# CoproMKII_Actuator.net
KiCad netlist of a schematic drawn in Altium Designer
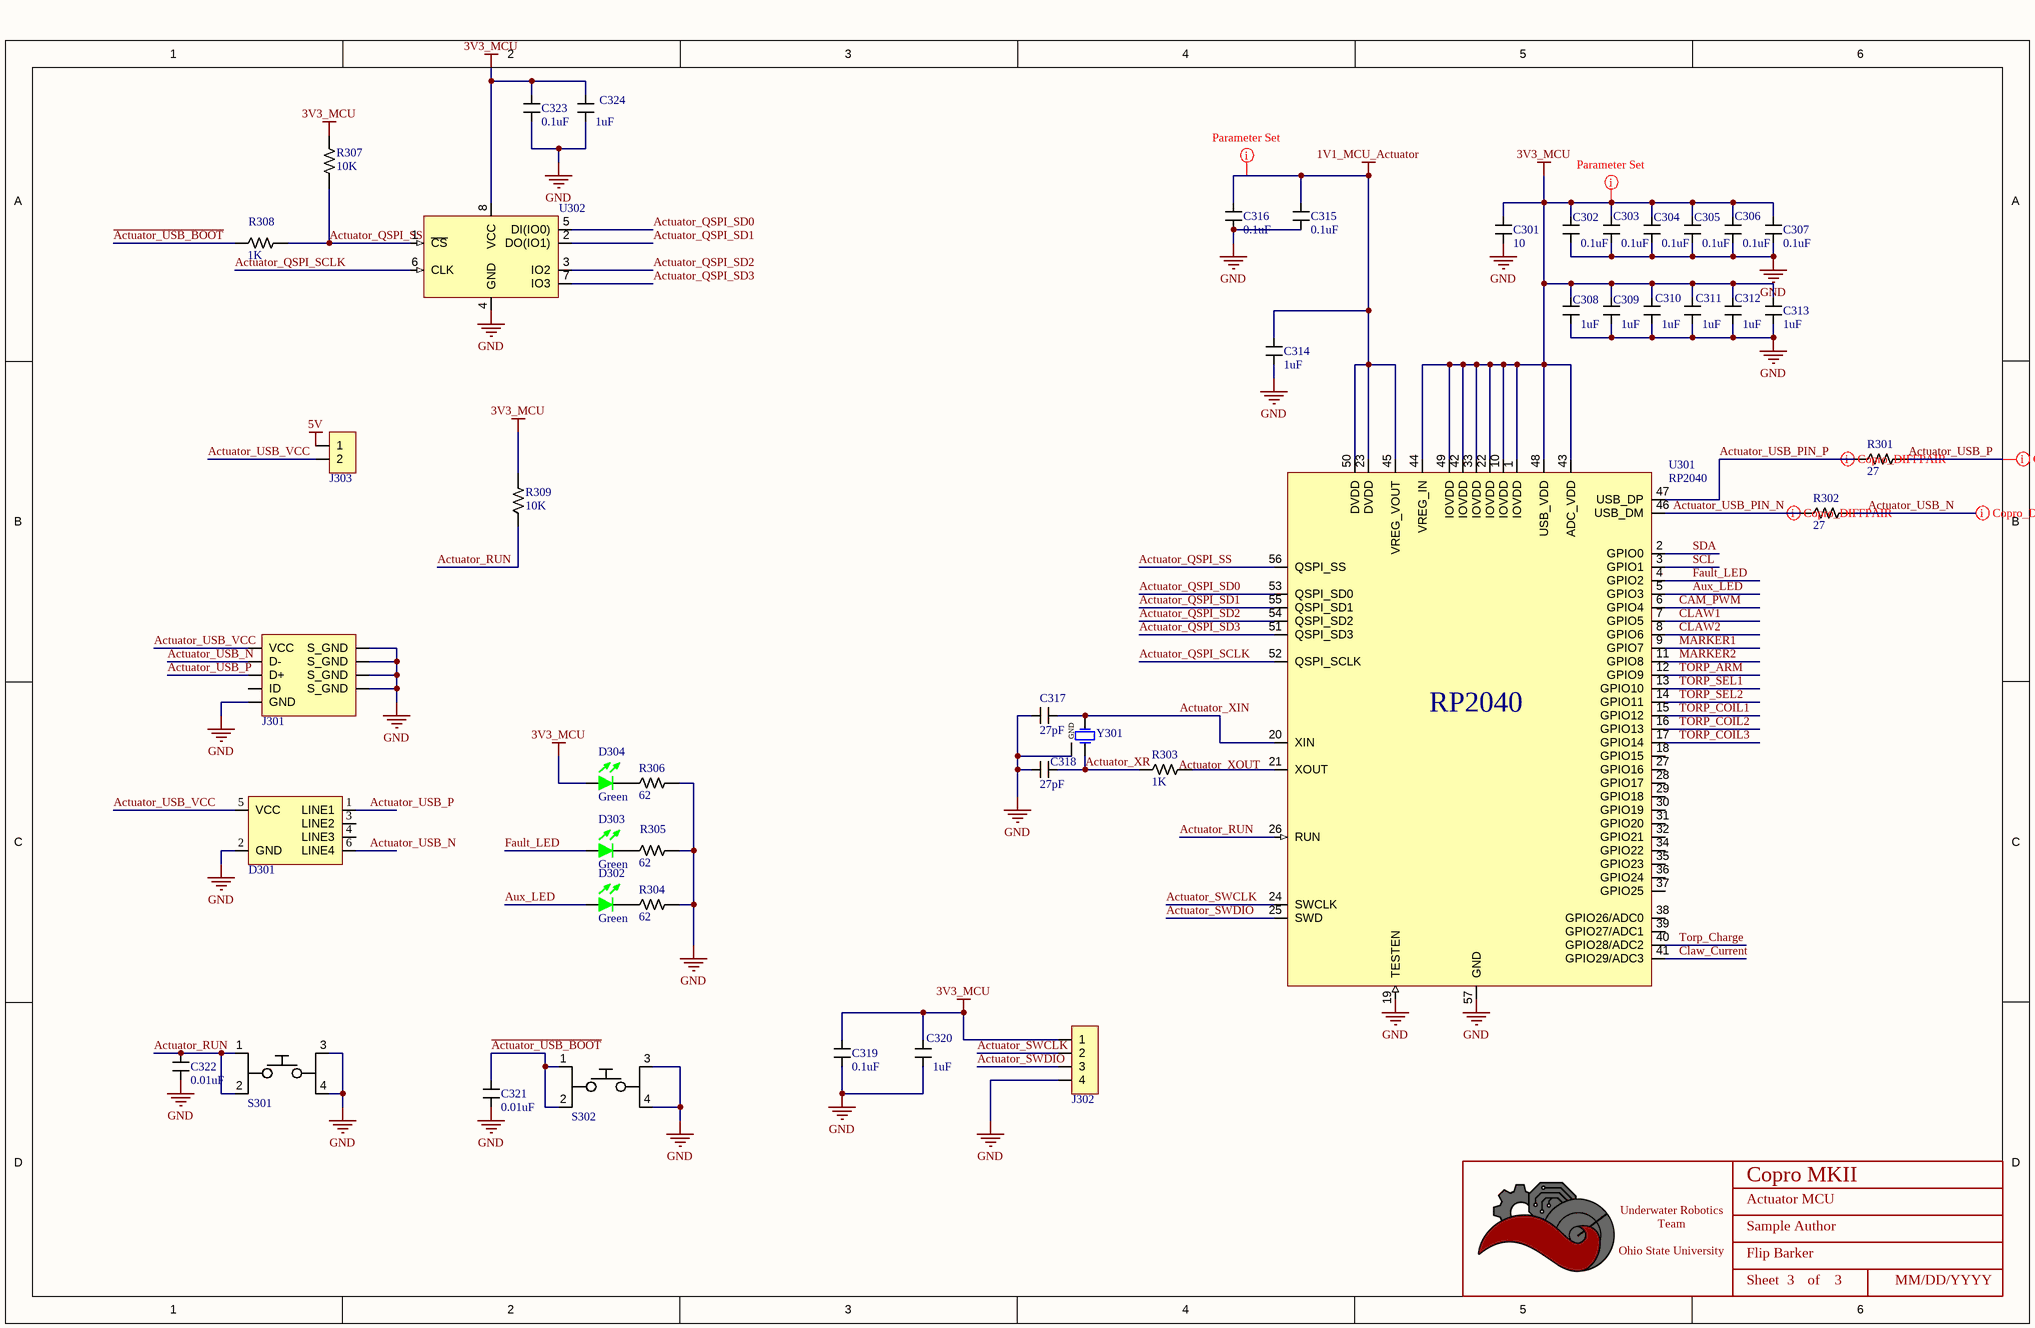
[diagram p0: CoproMKII_Actuator.SchDoc]

(export (version "E")
  (design (tool "Eeschema 10.0.6"))
  (components
    (comp (ref "C301")
      (value "10uF Ceramic 6.3V")
      (footprint "CAPACITOR_0603")
      (description "Cap 10uF 6.3V +/-20%\r\nCeramic 0603")
      (fields
        (field (name "TOLERANCE") "+/- 20%")
        (field (name "VOLTAGE") "6.3V")
        (field (name "VALUE (UF)") "10")
        (field (name "MADE BY") "Flip B")
      )
      (libsource (lib "Capacitors") (part "CAPACITOR_10uF_0603"))
    )
    (comp (ref "C302")
      (value "0.1uF")
      (footprint "CAPACITOR_0603")
      (description "Cap 100nF 6.3V +/-10%\r\nCeramic 0603")
      (fields
        (field (name "TOLERANCE") "+/- 10%")
        (field (name "VOLTAGE") "6.3V")
        (field (name "MADE BY") "Flip B")
      )
      (libsource (lib "Capacitors") (part "CAPACITOR_0.1uF_0603"))
    )
    (comp (ref "C303")
      (value "0.1uF")
      (footprint "CAPACITOR_0603")
      (description "Cap 100nF 6.3V +/-10%\r\nCeramic 0603")
      (fields
        (field (name "TOLERANCE") "+/- 10%")
        (field (name "VOLTAGE") "6.3V")
        (field (name "MADE BY") "Flip B")
      )
      (libsource (lib "Capacitors") (part "CAPACITOR_0.1uF_0603"))
    )
    (comp (ref "C304")
      (value "0.1uF")
      (footprint "CAPACITOR_0603")
      (description "Cap 100nF 6.3V +/-10%\r\nCeramic 0603")
      (fields
        (field (name "TOLERANCE") "+/- 10%")
        (field (name "VOLTAGE") "6.3V")
        (field (name "MADE BY") "Flip B")
      )
      (libsource (lib "Capacitors") (part "CAPACITOR_0.1uF_0603"))
    )
    (comp (ref "C305")
      (value "0.1uF")
      (footprint "CAPACITOR_0603")
      (description "Cap 100nF 6.3V +/-10%\r\nCeramic 0603")
      (fields
        (field (name "TOLERANCE") "+/- 10%")
        (field (name "VOLTAGE") "6.3V")
        (field (name "MADE BY") "Flip B")
      )
      (libsource (lib "Capacitors") (part "CAPACITOR_0.1uF_0603"))
    )
    (comp (ref "C306")
      (value "0.1uF")
      (footprint "CAPACITOR_0603")
      (description "Cap 100nF 6.3V +/-10%\r\nCeramic 0603")
      (fields
        (field (name "TOLERANCE") "+/- 10%")
        (field (name "VOLTAGE") "6.3V")
        (field (name "MADE BY") "Flip B")
      )
      (libsource (lib "Capacitors") (part "CAPACITOR_0.1uF_0603"))
    )
    (comp (ref "C307")
      (value "0.1uF")
      (footprint "CAPACITOR_0603")
      (description "Cap 100nF 6.3V +/-10%\r\nCeramic 0603")
      (fields
        (field (name "TOLERANCE") "+/- 10%")
        (field (name "VOLTAGE") "6.3V")
        (field (name "MADE BY") "Flip B")
      )
      (libsource (lib "Capacitors") (part "CAPACITOR_0.1uF_0603"))
    )
    (comp (ref "C308")
      (value "1uF")
      (footprint "CAPACITOR_0603")
      (description "Cap 1uF 16V +/-10%\r\nCeramic 0603")
      (fields
        (field (name "TOLERANCE") "+/- 10%")
        (field (name "VOLTAGE") "16V")
        (field (name "MADE BY") "Flip B")
      )
      (libsource (lib "Capacitors") (part "CAPACITOR_1uF_0603"))
    )
    (comp (ref "C309")
      (value "1uF")
      (footprint "CAPACITOR_0603")
      (description "Cap 1uF 16V +/-10%\r\nCeramic 0603")
      (fields
        (field (name "TOLERANCE") "+/- 10%")
        (field (name "VOLTAGE") "16V")
        (field (name "MADE BY") "Flip B")
      )
      (libsource (lib "Capacitors") (part "CAPACITOR_1uF_0603"))
    )
    (comp (ref "C310")
      (value "1uF")
      (footprint "CAPACITOR_0603")
      (description "Cap 1uF 16V +/-10%\r\nCeramic 0603")
      (fields
        (field (name "TOLERANCE") "+/- 10%")
        (field (name "VOLTAGE") "16V")
        (field (name "MADE BY") "Flip B")
      )
      (libsource (lib "Capacitors") (part "CAPACITOR_1uF_0603"))
    )
    (comp (ref "C311")
      (value "1uF")
      (footprint "CAPACITOR_0603")
      (description "Cap 1uF 16V +/-10%\r\nCeramic 0603")
      (fields
        (field (name "TOLERANCE") "+/- 10%")
        (field (name "VOLTAGE") "16V")
        (field (name "MADE BY") "Flip B")
      )
      (libsource (lib "Capacitors") (part "CAPACITOR_1uF_0603"))
    )
    (comp (ref "C312")
      (value "1uF")
      (footprint "CAPACITOR_0603")
      (description "Cap 1uF 16V +/-10%\r\nCeramic 0603")
      (fields
        (field (name "TOLERANCE") "+/- 10%")
        (field (name "VOLTAGE") "16V")
        (field (name "MADE BY") "Flip B")
      )
      (libsource (lib "Capacitors") (part "CAPACITOR_1uF_0603"))
    )
    (comp (ref "C313")
      (value "1uF")
      (footprint "CAPACITOR_0603")
      (description "Cap 1uF 16V +/-10%\r\nCeramic 0603")
      (fields
        (field (name "TOLERANCE") "+/- 10%")
        (field (name "VOLTAGE") "16V")
        (field (name "MADE BY") "Flip B")
      )
      (libsource (lib "Capacitors") (part "CAPACITOR_1uF_0603"))
    )
    (comp (ref "C314")
      (value "1uF")
      (footprint "CAPACITOR_0603")
      (description "Cap 1uF 16V +/-10%\r\nCeramic 0603")
      (fields
        (field (name "TOLERANCE") "+/- 10%")
        (field (name "VOLTAGE") "16V")
        (field (name "MADE BY") "Flip B")
      )
      (libsource (lib "Capacitors") (part "CAPACITOR_1uF_0603"))
    )
    (comp (ref "C315")
      (value "0.1uF")
      (footprint "CAPACITOR_0603")
      (description "Cap 100nF 6.3V +/-10%\r\nCeramic 0603")
      (fields
        (field (name "TOLERANCE") "+/- 10%")
        (field (name "VOLTAGE") "6.3V")
        (field (name "MADE BY") "Flip B")
      )
      (libsource (lib "Capacitors") (part "CAPACITOR_0.1uF_0603"))
    )
    (comp (ref "C316")
      (value "0.1uF")
      (footprint "CAPACITOR_0603")
      (description "Cap 100nF 6.3V +/-10%\r\nCeramic 0603")
      (fields
        (field (name "TOLERANCE") "+/- 10%")
        (field (name "VOLTAGE") "6.3V")
        (field (name "MADE BY") "Flip B")
      )
      (libsource (lib "Capacitors") (part "CAPACITOR_0.1uF_0603"))
    )
    (comp (ref "C317")
      (value "27pF")
      (footprint "CAPACITOR_0603")
      (description "Cap 27pF 50V +/-5%\r\nCeramic 0603")
      (fields
        (field (name "TOLERANCE") "+/- 5%")
        (field (name "VOLTAGE") "50V")
        (field (name "MADE BY") "Flip B")
      )
      (libsource (lib "Capacitors") (part "CAPACITOR_0.000027uF_0603"))
    )
    (comp (ref "C318")
      (value "27pF")
      (footprint "CAPACITOR_0603")
      (description "Cap 27pF 50V +/-5%\r\nCeramic 0603")
      (fields
        (field (name "TOLERANCE") "+/- 5%")
        (field (name "VOLTAGE") "50V")
        (field (name "MADE BY") "Flip B")
      )
      (libsource (lib "Capacitors") (part "CAPACITOR_0.000027uF_0603"))
    )
    (comp (ref "C319")
      (value "0.1uF")
      (footprint "CAPACITOR_0603")
      (description "Cap 100nF 6.3V +/-10%\r\nCeramic 0603")
      (fields
        (field (name "TOLERANCE") "+/- 10%")
        (field (name "VOLTAGE") "6.3V")
        (field (name "MADE BY") "Flip B")
      )
      (libsource (lib "Capacitors") (part "CAPACITOR_0.1uF_0603"))
    )
    (comp (ref "C320")
      (value "1uF")
      (footprint "CAPACITOR_0603")
      (description "Cap 1uF 16V +/-10%\r\nCeramic 0603")
      (fields
        (field (name "TOLERANCE") "+/- 10%")
        (field (name "VOLTAGE") "16V")
        (field (name "MADE BY") "Flip B")
      )
      (libsource (lib "Capacitors") (part "CAPACITOR_1uF_0603"))
    )
    (comp (ref "C321")
      (value "0.01uF")
      (footprint "CAPACITOR_0603")
      (description "Cap 10nF 6.3V +/-20%\r\nCeramic 0603")
      (fields
        (field (name "TOLERANCE") "+/- 10%")
        (field (name "VOLTAGE") "6.3V")
        (field (name "MADE BY") "Flip B")
      )
      (libsource (lib "Capacitors") (part "CAPACITOR_0.01uF_0603"))
    )
    (comp (ref "C322")
      (value "0.01uF")
      (footprint "CAPACITOR_0603")
      (description "Cap 10nF 6.3V +/-20%\r\nCeramic 0603")
      (fields
        (field (name "TOLERANCE") "+/- 10%")
        (field (name "VOLTAGE") "6.3V")
        (field (name "MADE BY") "Flip B")
      )
      (libsource (lib "Capacitors") (part "CAPACITOR_0.01uF_0603"))
    )
    (comp (ref "C323")
      (value "0.1uF")
      (footprint "CAPACITOR_0603")
      (description "Cap 100nF 6.3V +/-10%\r\nCeramic 0603")
      (fields
        (field (name "TOLERANCE") "+/- 10%")
        (field (name "VOLTAGE") "6.3V")
        (field (name "MADE BY") "Flip B")
      )
      (libsource (lib "Capacitors") (part "CAPACITOR_0.1uF_0603"))
    )
    (comp (ref "C324")
      (value "1uF")
      (footprint "CAPACITOR_0603")
      (description "Cap 1uF 16V +/-10%\r\nCeramic 0603")
      (fields
        (field (name "TOLERANCE") "+/- 10%")
        (field (name "VOLTAGE") "16V")
        (field (name "MADE BY") "Flip B")
      )
      (libsource (lib "Capacitors") (part "CAPACITOR_1uF_0603"))
    )
    (comp (ref "D301")
      (value "TVS DIODE 5VWM 25VC SOT23-6")
      (footprint "SOT 23-6L")
      (description "25V Clamp 6A (8/20µs) Ipp Tvs Diode Surface Mount SOT-23-6")
      (fields (field (name "MADE BY") "Robert Pafford"))
      (libsource (lib "Diodes") (part "RCLAMP0504S.TCT"))
    )
    (comp (ref "D302")
      (value "IN-S63AT5G")
      (footprint "LED_0603")
      (description "LED Green Vf= 3V If = 0.005A\r\nIN-S63AT5G")
      (fields (field (name "COLOR") "Green") (field (name "MADE BY") "Robert Pafford"))
      (libsource (lib "Diodes") (part "LED_Green_0603_3V"))
    )
    (comp (ref "D303")
      (value "IN-S63AT5G")
      (footprint "LED_0603")
      (description "LED Green Vf= 3V If = 0.005A\r\nIN-S63AT5G")
      (fields (field (name "COLOR") "Green") (field (name "MADE BY") "Robert Pafford"))
      (libsource (lib "Diodes") (part "LED_Green_0603_3V"))
    )
    (comp (ref "D304")
      (value "IN-S63AT5G")
      (footprint "LED_0603")
      (description "LED Green Vf= 3V If = 0.005A\r\nIN-S63AT5G")
      (fields (field (name "COLOR") "Green") (field (name "MADE BY") "Robert Pafford"))
      (libsource (lib "Diodes") (part "LED_Green_0603_3V"))
    )
    (comp (ref "J301")
      (value "USB_MICRO R/A")
      (footprint "CONN_MINIUSB")
      (description "Amphenol Micro USB-B\r\nUSB2.0 5 Pin Right Angle SMD")
      (fields (field (name "MANUFACTURER") "Amphenol") (field (name "CREATED BY") "Flip B"))
      (libsource (lib "Connectors") (part "CONN_MICROUSB"))
    )
    (comp (ref "J302")
      (value "CONN HEADER VERT 4POS 2.54MM")
      (footprint "HEADER_4PIN_2.54MM")
      (fields (field (name "MADE BY") "Robert Pafford"))
      (libsource (lib "Connectors") (part "HEADER_4PIN_2.54MM"))
    )
    (comp (ref "J303")
      (value "2 POS")
      (footprint "HEADER_2PIN_2.54MM")
      (description "CONN HEADER VERT 2POS 2.54MM")
      (fields (field (name "CREATED BY") "Robert P"))
      (libsource (lib "Connectors") (part "HEADER_2PIN_2.54MM"))
    )
    (comp (ref "R301")
      (value "27 Ohm 5% 1/8W")
      (footprint "RESISTOR_0603")
      (description "RES 27 OHM 5% 1/8W 0603")
      (fields
        (field (name "TOLERANCE") "+/- 5%")
        (field (name "VALUE  (OHMS)") "27")
        (field (name "MADE BY") "Robert Pafford")
      )
      (libsource (lib "Resistors") (part "RESISTOR_27_0603"))
    )
    (comp (ref "R302")
      (value "27 Ohm 5% 1/8W")
      (footprint "RESISTOR_0603")
      (description "RES 27 OHM 5% 1/8W 0603")
      (fields
        (field (name "TOLERANCE") "+/- 5%")
        (field (name "VALUE  (OHMS)") "27")
        (field (name "MADE BY") "Robert Pafford")
      )
      (libsource (lib "Resistors") (part "RESISTOR_27_0603"))
    )
    (comp (ref "R303")
      (value "1k Ohm 5% 1/8W")
      (footprint "RESISTOR_0603")
      (description "RES 1k OHM 5% 1/8W 0603")
      (fields
        (field (name "TOLERANCE") "+/- 5%")
        (field (name "VALUE  (OHMS)") "1K")
        (field (name "MADE BY") "Robert Pafford")
      )
      (libsource (lib "Resistors") (part "RESISTOR_1K_0603"))
    )
    (comp (ref "R304")
      (value "62 Ohm 1% 1/4W")
      (footprint "RESISTOR_0603")
      (description "RES SMD 62 OHM 1% 1/4W 0603")
      (fields
        (field (name "TOLERANCE") "+/- 1%")
        (field (name "VALUE  (OHMS)") "62")
        (field (name "MADE BY") "Robert Pafford")
      )
      (libsource (lib "Resistors") (part "RESISTOR_62_0603"))
    )
    (comp (ref "R305")
      (value "62 Ohm 1% 1/4W")
      (footprint "RESISTOR_0603")
      (description "RES SMD 62 OHM 1% 1/4W 0603")
      (fields
        (field (name "TOLERANCE") "+/- 1%")
        (field (name "VALUE  (OHMS)") "62")
        (field (name "MADE BY") "Robert Pafford")
      )
      (libsource (lib "Resistors") (part "RESISTOR_62_0603"))
    )
    (comp (ref "R306")
      (value "62 Ohm 1% 1/4W")
      (footprint "RESISTOR_0603")
      (description "RES SMD 62 OHM 1% 1/4W 0603")
      (fields
        (field (name "TOLERANCE") "+/- 1%")
        (field (name "VALUE  (OHMS)") "62")
        (field (name "MADE BY") "Robert Pafford")
      )
      (libsource (lib "Resistors") (part "RESISTOR_62_0603"))
    )
    (comp (ref "R307")
      (value "10k Ohm 5% 1/10W")
      (footprint "RESISTOR_0603")
      (description "RES 10k OHM 5% 1/10W 0603")
      (fields
        (field (name "TOLERANCE") "+/- 5%")
        (field (name "VALUE  (OHMS)") "10K")
        (field (name "MADE BY") "Robert Pafford")
      )
      (libsource (lib "Resistors") (part "RESISTOR_10K_0603"))
    )
    (comp (ref "R308")
      (value "1k Ohm 5% 1/8W")
      (footprint "RESISTOR_0603")
      (description "RES 1k OHM 5% 1/8W 0603")
      (fields
        (field (name "TOLERANCE") "+/- 5%")
        (field (name "VALUE  (OHMS)") "1K")
        (field (name "MADE BY") "Robert Pafford")
      )
      (libsource (lib "Resistors") (part "RESISTOR_1K_0603"))
    )
    (comp (ref "R309")
      (value "10k Ohm 5% 1/10W")
      (footprint "RESISTOR_0603")
      (description "RES 10k OHM 5% 1/10W 0603")
      (fields
        (field (name "TOLERANCE") "+/- 5%")
        (field (name "VALUE  (OHMS)") "10K")
        (field (name "MADE BY") "Robert Pafford")
      )
      (libsource (lib "Resistors") (part "RESISTOR_10K_0603"))
    )
    (comp (ref "S301")
      (value "SPST Tactile Switch")
      (footprint "TactileSwitch")
      (description "SWITCH TACTILE SPST-NO 0.05A 12V")
      (fields (field (name "MADE BY") "Robert Pafford"))
      (libsource (lib "Switches") (part "Tactile Switch"))
    )
    (comp (ref "S302")
      (value "SPST Tactile Switch")
      (footprint "TactileSwitch")
      (description "SWITCH TACTILE SPST-NO 0.05A 12V")
      (fields (field (name "MADE BY") "Robert Pafford"))
      (libsource (lib "Switches") (part "Tactile Switch"))
    )
    (comp (ref "U301")
      (value "RP2040")
      (footprint "QFN-56 RP2040")
      (description "Raspberry Pi RP2040")
      (fields (field (name "MADE BY") "Robert Pafford"))
      (libsource (lib "Integrated Circuits") (part "RP2040"))
    )
    (comp (ref "U302")
      (value "W25Q128JVSIQ")
      (footprint "SOIC-8 W25QxJV")
      (description "IC FLASH 128MBIT SPI/QUAD 8SOIC")
      (fields (field (name "MADE BY") "Robert Pafford"))
      (libsource (lib "Integrated Circuits") (part "W25Q128JVSIQ"))
    )
    (comp (ref "Y301")
      (value "CRYSTAL 12.0000MHZ 18PF SMD")
      (footprint "4-SMD No Lead Crystal")
      (description "12 MHz ±20ppm Crystal 18pF 50 Ohms 4-SMD, No Lead")
      (fields (field (name "MADE BY") "Siddharth Venkatesan"))
      (libsource (lib "Crystals") (part "CRYSTAL_12MHz_SMD"))
    )
  )
  (nets
    (net (code "1") (name "/Actuator_QSPI_SCLK") (class "Default")
      (node (ref "U301") (pin "52") (pinfunction "QSPI_SCLK_52") (pintype "bidirectional"))
      (node (ref "U302") (pin "6") (pinfunction "CLK_6") (pintype "input"))
    )
    (net (code "2") (name "/Actuator_QSPI_SD0") (class "Default")
      (node (ref "U301") (pin "53") (pinfunction "QSPI_SD0_53") (pintype "bidirectional"))
      (node (ref "U302") (pin "5") (pinfunction "DI(IO0)_5") (pintype "bidirectional"))
    )
    (net (code "3") (name "/Actuator_QSPI_SD1") (class "Default")
      (node (ref "U301") (pin "55") (pinfunction "QSPI_SD1_55") (pintype "bidirectional"))
      (node (ref "U302") (pin "2") (pinfunction "DO(IO1)_2") (pintype "bidirectional"))
    )
    (net (code "4") (name "/Actuator_QSPI_SD2") (class "Default")
      (node (ref "U301") (pin "54") (pinfunction "QSPI_SD2_54") (pintype "bidirectional"))
      (node (ref "U302") (pin "3") (pinfunction "IO2_3") (pintype "bidirectional"))
    )
    (net (code "5") (name "/Actuator_QSPI_SD3") (class "Default")
      (node (ref "U301") (pin "51") (pinfunction "QSPI_SD3_51") (pintype "bidirectional"))
      (node (ref "U302") (pin "7") (pinfunction "IO3_7") (pintype "bidirectional"))
    )
    (net (code "6") (name "/Actuator_QSPI_SS") (class "Default")
      (node (ref "R307") (pin "1") (pinfunction "1_1") (pintype "passive"))
      (node (ref "R308") (pin "1") (pinfunction "1_1") (pintype "passive"))
      (node (ref "U301") (pin "56") (pinfunction "QSPI_SS_56") (pintype "bidirectional"))
      (node (ref "U302") (pin "1") (pinfunction "~{CS}_1") (pintype "input"))
    )
    (net (code "7") (name "/Actuator_RUN") (class "Default")
      (node (ref "C322") (pin "1") (pinfunction "1_1") (pintype "passive"))
      (node (ref "R309") (pin "2") (pinfunction "2_2") (pintype "passive"))
      (node (ref "S301") (pin "1") (pinfunction "1_1") (pintype "passive"))
      (node (ref "S301") (pin "2") (pinfunction "2_2") (pintype "passive"))
      (node (ref "U301") (pin "26") (pinfunction "RUN_26") (pintype "input"))
    )
    (net (code "8") (name "/Actuator_SWCLK") (class "Default")
      (node (ref "J302") (pin "2") (pinfunction "2_2") (pintype "passive"))
      (node (ref "U301") (pin "24") (pinfunction "SWCLK_24") (pintype "bidirectional"))
    )
    (net (code "9") (name "/Actuator_SWDIO") (class "Default")
      (node (ref "J302") (pin "3") (pinfunction "3_3") (pintype "passive"))
      (node (ref "U301") (pin "25") (pinfunction "SWD_25") (pintype "bidirectional"))
    )
    (net (code "10") (name "/Actuator_USB_N") (class "Default")
      (node (ref "D301") (pin "6") (pinfunction "LINE4_6") (pintype "passive"))
      (node (ref "J301") (pin "2") (pinfunction "D-_2") (pintype "passive"))
      (node (ref "R302") (pin "1") (pinfunction "1_1") (pintype "passive"))
    )
    (net (code "11") (name "/Actuator_USB_P") (class "Default")
      (node (ref "D301") (pin "1") (pinfunction "LINE1_1") (pintype "passive"))
      (node (ref "J301") (pin "3") (pinfunction "D+_3") (pintype "passive"))
      (node (ref "R301") (pin "1") (pinfunction "1_1") (pintype "passive"))
    )
    (net (code "12") (name "/Actuator_USB_PIN_N") (class "Default")
      (node (ref "R302") (pin "2") (pinfunction "2_2") (pintype "passive"))
      (node (ref "U301") (pin "46") (pinfunction "USB_DM_46") (pintype "bidirectional"))
    )
    (net (code "13") (name "/Actuator_USB_PIN_P") (class "Default")
      (node (ref "R301") (pin "2") (pinfunction "2_2") (pintype "passive"))
      (node (ref "U301") (pin "47") (pinfunction "USB_DP_47") (pintype "bidirectional"))
    )
    (net (code "14") (name "/Actuator_USB_VCC") (class "Default")
      (node (ref "D301") (pin "5") (pinfunction "VCC_5") (pintype "power_in"))
      (node (ref "J301") (pin "1") (pinfunction "VCC_1") (pintype "passive"))
      (node (ref "J303") (pin "2") (pinfunction "2_2") (pintype "passive"))
    )
    (net (code "15") (name "/Actuator_XIN") (class "Default")
      (node (ref "C317") (pin "1") (pinfunction "1_1") (pintype "passive"))
      (node (ref "U301") (pin "20") (pinfunction "XIN_20") (pintype "passive"))
      (node (ref "Y301") (pin "1") (pinfunction "1_1") (pintype "passive"))
    )
    (net (code "17") (name "/Actuator_XR") (class "Default")
      (node (ref "C318") (pin "1") (pinfunction "1_1") (pintype "passive"))
      (node (ref "R303") (pin "2") (pinfunction "2_2") (pintype "passive"))
      (node (ref "Y301") (pin "2") (pinfunction "2_2") (pintype "passive"))
    )
    (net (code "18") (name "/Aux_LED") (class "Default")
      (node (ref "D302") (pin "1") (pinfunction "1_1") (pintype "passive"))
      (node (ref "U301") (pin "5") (pinfunction "GPIO3_5") (pintype "bidirectional"))
    )
    (net (code "19") (name "/CAM_PWM") (class "Default")
      (node (ref "U301") (pin "6") (pinfunction "GPIO4_6") (pintype "bidirectional"))
    )
    (net (code "20") (name "/CLAW1") (class "Default")
      (node (ref "U301") (pin "7") (pinfunction "GPIO5_7") (pintype "bidirectional"))
    )
    (net (code "21") (name "/CLAW2") (class "Default")
      (node (ref "U301") (pin "8") (pinfunction "GPIO6_8") (pintype "bidirectional"))
    )
    (net (code "22") (name "/Claw_Current") (class "Default")
      (node (ref "U301") (pin "41") (pinfunction "GPIO29/ADC3_41") (pintype "bidirectional"))
    )
    (net (code "23") (name "/Fault_LED") (class "Default")
      (node (ref "D303") (pin "1") (pinfunction "1_1") (pintype "passive"))
      (node (ref "U301") (pin "4") (pinfunction "GPIO2_4") (pintype "bidirectional"))
    )
    (net (code "24") (name "/MARKER1") (class "Default")
      (node (ref "U301") (pin "9") (pinfunction "GPIO7_9") (pintype "bidirectional"))
    )
    (net (code "25") (name "/MARKER2") (class "Default")
      (node (ref "U301") (pin "11") (pinfunction "GPIO8_11") (pintype "bidirectional"))
    )
    (net (code "26") (name "/SCL") (class "Default")
      (node (ref "U301") (pin "3") (pinfunction "GPIO1_3") (pintype "bidirectional"))
    )
    (net (code "27") (name "/SDA") (class "Default")
      (node (ref "U301") (pin "2") (pinfunction "GPIO0_2") (pintype "bidirectional"))
    )
    (net (code "28") (name "/TORP_ARM") (class "Default")
      (node (ref "U301") (pin "12") (pinfunction "GPIO9_12") (pintype "bidirectional"))
    )
    (net (code "29") (name "/TORP_COIL1") (class "Default")
      (node (ref "U301") (pin "15") (pinfunction "GPIO12_15") (pintype "bidirectional"))
    )
    (net (code "30") (name "/TORP_COIL2") (class "Default")
      (node (ref "U301") (pin "16") (pinfunction "GPIO13_16") (pintype "bidirectional"))
    )
    (net (code "31") (name "/TORP_COIL3") (class "Default")
      (node (ref "U301") (pin "17") (pinfunction "GPIO14_17") (pintype "bidirectional"))
    )
    (net (code "32") (name "/TORP_SEL1") (class "Default")
      (node (ref "U301") (pin "13") (pinfunction "GPIO10_13") (pintype "bidirectional"))
    )
    (net (code "33") (name "/TORP_SEL2") (class "Default")
      (node (ref "U301") (pin "14") (pinfunction "GPIO11_14") (pintype "bidirectional"))
    )
    (net (code "34") (name "/Torp_Charge") (class "Default")
      (node (ref "U301") (pin "40") (pinfunction "GPIO28/ADC2_40") (pintype "bidirectional"))
    )
    (net (code "35") (name "/~{Actuator_USB_BOOT}") (class "Default")
      (node (ref "C321") (pin "1") (pinfunction "1_1") (pintype "passive"))
      (node (ref "R308") (pin "2") (pinfunction "2_2") (pintype "passive"))
      (node (ref "S302") (pin "1") (pinfunction "1_1") (pintype "passive"))
      (node (ref "S302") (pin "2") (pinfunction "2_2") (pintype "passive"))
    )
    (net (code "36") (name "1V1_MCU_Actuator") (class "Default")
      (node (ref "C314") (pin "2") (pinfunction "2_2") (pintype "passive"))
      (node (ref "C315") (pin "2") (pinfunction "2_2") (pintype "passive"))
      (node (ref "C316") (pin "2") (pinfunction "2_2") (pintype "passive"))
      (node (ref "U301") (pin "23") (pinfunction "DVDD_23") (pintype "power_in"))
      (node (ref "U301") (pin "45") (pinfunction "VREG_VOUT_45") (pintype "power_in"))
      (node (ref "U301") (pin "50") (pinfunction "DVDD_50") (pintype "power_in"))
    )
    (net (code "37") (name "3V3_MCU") (class "Default")
      (node (ref "C301") (pin "2") (pinfunction "2_2") (pintype "passive"))
      (node (ref "C302") (pin "2") (pinfunction "2_2") (pintype "passive"))
      (node (ref "C303") (pin "2") (pinfunction "2_2") (pintype "passive"))
      (node (ref "C304") (pin "2") (pinfunction "2_2") (pintype "passive"))
      (node (ref "C305") (pin "2") (pinfunction "2_2") (pintype "passive"))
      (node (ref "C306") (pin "2") (pinfunction "2_2") (pintype "passive"))
      (node (ref "C307") (pin "2") (pinfunction "2_2") (pintype "passive"))
      (node (ref "C308") (pin "2") (pinfunction "2_2") (pintype "passive"))
      (node (ref "C309") (pin "2") (pinfunction "2_2") (pintype "passive"))
      (node (ref "C310") (pin "2") (pinfunction "2_2") (pintype "passive"))
      (node (ref "C311") (pin "2") (pinfunction "2_2") (pintype "passive"))
      (node (ref "C312") (pin "2") (pinfunction "2_2") (pintype "passive"))
      (node (ref "C313") (pin "2") (pinfunction "2_2") (pintype "passive"))
      (node (ref "C319") (pin "1") (pinfunction "1_1") (pintype "passive"))
      (node (ref "C320") (pin "1") (pinfunction "1_1") (pintype "passive"))
      (node (ref "C323") (pin "1") (pinfunction "1_1") (pintype "passive"))
      (node (ref "C324") (pin "1") (pinfunction "1_1") (pintype "passive"))
      (node (ref "D304") (pin "1") (pinfunction "1_1") (pintype "passive"))
      (node (ref "J302") (pin "1") (pinfunction "1_1") (pintype "passive"))
      (node (ref "R307") (pin "2") (pinfunction "2_2") (pintype "passive"))
      (node (ref "R309") (pin "1") (pinfunction "1_1") (pintype "passive"))
      (node (ref "U301") (pin "1") (pinfunction "IOVDD_1") (pintype "power_in"))
      (node (ref "U301") (pin "10") (pinfunction "IOVDD_10") (pintype "power_in"))
      (node (ref "U301") (pin "22") (pinfunction "IOVDD_22") (pintype "power_in"))
      (node (ref "U301") (pin "33") (pinfunction "IOVDD_33") (pintype "power_in"))
      (node (ref "U301") (pin "42") (pinfunction "IOVDD_42") (pintype "power_in"))
      (node (ref "U301") (pin "43") (pinfunction "ADC_VDD_43") (pintype "power_in"))
      (node (ref "U301") (pin "44") (pinfunction "VREG_IN_44") (pintype "power_in"))
      (node (ref "U301") (pin "48") (pinfunction "USB_VDD_48") (pintype "power_in"))
      (node (ref "U301") (pin "49") (pinfunction "IOVDD_49") (pintype "power_in"))
      (node (ref "U302") (pin "8") (pinfunction "VCC_8") (pintype "power_in"))
    )
    (net (code "38") (name "5V") (class "Default")
      (node (ref "J303") (pin "1") (pinfunction "1_1") (pintype "passive"))
    )
    (net (code "39") (name "GND") (class "Default")
      (node (ref "C301") (pin "1") (pinfunction "1_1") (pintype "passive"))
      (node (ref "C302") (pin "1") (pinfunction "1_1") (pintype "passive"))
      (node (ref "C303") (pin "1") (pinfunction "1_1") (pintype "passive"))
      (node (ref "C304") (pin "1") (pinfunction "1_1") (pintype "passive"))
      (node (ref "C305") (pin "1") (pinfunction "1_1") (pintype "passive"))
      (node (ref "C306") (pin "1") (pinfunction "1_1") (pintype "passive"))
      (node (ref "C307") (pin "1") (pinfunction "1_1") (pintype "passive"))
      (node (ref "C308") (pin "1") (pinfunction "1_1") (pintype "passive"))
      (node (ref "C309") (pin "1") (pinfunction "1_1") (pintype "passive"))
      (node (ref "C310") (pin "1") (pinfunction "1_1") (pintype "passive"))
      (node (ref "C311") (pin "1") (pinfunction "1_1") (pintype "passive"))
      (node (ref "C312") (pin "1") (pinfunction "1_1") (pintype "passive"))
      (node (ref "C313") (pin "1") (pinfunction "1_1") (pintype "passive"))
      (node (ref "C314") (pin "1") (pinfunction "1_1") (pintype "passive"))
      (node (ref "C315") (pin "1") (pinfunction "1_1") (pintype "passive"))
      (node (ref "C316") (pin "1") (pinfunction "1_1") (pintype "passive"))
      (node (ref "C317") (pin "2") (pinfunction "2_2") (pintype "passive"))
      (node (ref "C318") (pin "2") (pinfunction "2_2") (pintype "passive"))
      (node (ref "C319") (pin "2") (pinfunction "2_2") (pintype "passive"))
      (node (ref "C320") (pin "2") (pinfunction "2_2") (pintype "passive"))
      (node (ref "C321") (pin "2") (pinfunction "2_2") (pintype "passive"))
      (node (ref "C322") (pin "2") (pinfunction "2_2") (pintype "passive"))
      (node (ref "C323") (pin "2") (pinfunction "2_2") (pintype "passive"))
      (node (ref "C324") (pin "2") (pinfunction "2_2") (pintype "passive"))
      (node (ref "D301") (pin "2") (pinfunction "GND_2") (pintype "power_in"))
      (node (ref "J301") (pin "5") (pinfunction "GND_5") (pintype "passive"))
      (node (ref "J301") (pin "6") (pinfunction "S_GND_6") (pintype "passive"))
      (node (ref "J301") (pin "7") (pinfunction "S_GND_7") (pintype "passive"))
      (node (ref "J301") (pin "8") (pinfunction "S_GND_8") (pintype "passive"))
      (node (ref "J301") (pin "9") (pinfunction "S_GND_9") (pintype "passive"))
      (node (ref "J302") (pin "4") (pinfunction "4_4") (pintype "passive"))
      (node (ref "R304") (pin "1") (pinfunction "1_1") (pintype "passive"))
      (node (ref "R305") (pin "1") (pinfunction "1_1") (pintype "passive"))
      (node (ref "R306") (pin "1") (pinfunction "1_1") (pintype "passive"))
      (node (ref "S301") (pin "3") (pinfunction "3_3") (pintype "passive"))
      (node (ref "S301") (pin "4") (pinfunction "4_4") (pintype "passive"))
      (node (ref "S302") (pin "3") (pinfunction "3_3") (pintype "passive"))
      (node (ref "S302") (pin "4") (pinfunction "4_4") (pintype "passive"))
      (node (ref "U301") (pin "19") (pinfunction "TESTEN_19") (pintype "input"))
      (node (ref "U301") (pin "57") (pinfunction "GND_57") (pintype "power_in"))
      (node (ref "U302") (pin "4") (pinfunction "GND_4") (pintype "power_in"))
      (node (ref "Y301") (pin "GND") (pinfunction "GND_GND") (pintype "power_in"))
    )
    (net (code "40") (name "Net-(D302-Pad2)") (class "Default")
      (node (ref "D302") (pin "2") (pinfunction "2_2") (pintype "passive"))
      (node (ref "R304") (pin "2") (pinfunction "2_2") (pintype "passive"))
    )
    (net (code "41") (name "Net-(D303-Pad2)") (class "Default")
      (node (ref "D303") (pin "2") (pinfunction "2_2") (pintype "passive"))
      (node (ref "R305") (pin "2") (pinfunction "2_2") (pintype "passive"))
    )
    (net (code "42") (name "Net-(D304-Pad2)") (class "Default")
      (node (ref "D304") (pin "2") (pinfunction "2_2") (pintype "passive"))
      (node (ref "R306") (pin "2") (pinfunction "2_2") (pintype "passive"))
    )
    (net (code "43") (name "Net-(U301-XOUT)") (class "Default")
      (node (ref "R303") (pin "1") (pinfunction "1_1") (pintype "passive"))
      (node (ref "U301") (pin "21") (pinfunction "XOUT_21") (pintype "passive"))
    )
    (net (code "44") (name "unconnected-(D301-LINE2-Pad3)") (class "Default")
      (node (ref "D301") (pin "3") (pinfunction "LINE2_3") (pintype "passive"))
    )
    (net (code "45") (name "unconnected-(D301-LINE3-Pad4)") (class "Default")
      (node (ref "D301") (pin "4") (pinfunction "LINE3_4") (pintype "passive"))
    )
    (net (code "46") (name "unconnected-(J301-ID-Pad4)") (class "Default")
      (node (ref "J301") (pin "4") (pinfunction "ID_4") (pintype "passive"))
    )
    (net (code "47") (name "unconnected-(U301-GPIO15-Pad18)") (class "Default")
      (node (ref "U301") (pin "18") (pinfunction "GPIO15_18") (pintype "bidirectional"))
    )
    (net (code "48") (name "unconnected-(U301-GPIO16-Pad27)") (class "Default")
      (node (ref "U301") (pin "27") (pinfunction "GPIO16_27") (pintype "bidirectional"))
    )
    (net (code "49") (name "unconnected-(U301-GPIO17-Pad28)") (class "Default")
      (node (ref "U301") (pin "28") (pinfunction "GPIO17_28") (pintype "bidirectional"))
    )
    (net (code "50") (name "unconnected-(U301-GPIO18-Pad29)") (class "Default")
      (node (ref "U301") (pin "29") (pinfunction "GPIO18_29") (pintype "bidirectional"))
    )
    (net (code "51") (name "unconnected-(U301-GPIO19-Pad30)") (class "Default")
      (node (ref "U301") (pin "30") (pinfunction "GPIO19_30") (pintype "bidirectional"))
    )
    (net (code "52") (name "unconnected-(U301-GPIO20-Pad31)") (class "Default")
      (node (ref "U301") (pin "31") (pinfunction "GPIO20_31") (pintype "bidirectional"))
    )
    (net (code "53") (name "unconnected-(U301-GPIO21-Pad32)") (class "Default")
      (node (ref "U301") (pin "32") (pinfunction "GPIO21_32") (pintype "bidirectional"))
    )
    (net (code "54") (name "unconnected-(U301-GPIO22-Pad34)") (class "Default")
      (node (ref "U301") (pin "34") (pinfunction "GPIO22_34") (pintype "bidirectional"))
    )
    (net (code "55") (name "unconnected-(U301-GPIO23-Pad35)") (class "Default")
      (node (ref "U301") (pin "35") (pinfunction "GPIO23_35") (pintype "bidirectional"))
    )
    (net (code "56") (name "unconnected-(U301-GPIO24-Pad36)") (class "Default")
      (node (ref "U301") (pin "36") (pinfunction "GPIO24_36") (pintype "bidirectional"))
    )
    (net (code "57") (name "unconnected-(U301-GPIO25-Pad37)") (class "Default")
      (node (ref "U301") (pin "37") (pinfunction "GPIO25_37") (pintype "bidirectional"))
    )
    (net (code "58") (name "unconnected-(U301-GPIO26{slash}ADC0-Pad38)") (class "Default")
      (node (ref "U301") (pin "38") (pinfunction "GPIO26/ADC0_38") (pintype "bidirectional"))
    )
    (net (code "59") (name "unconnected-(U301-GPIO27{slash}ADC1-Pad39)") (class "Default")
      (node (ref "U301") (pin "39") (pinfunction "GPIO27/ADC1_39") (pintype "bidirectional"))
    )
  )
)
